# RP2040_Evaluation_Design.net
KiCad netlist of a schematic drawn in Altium Designer
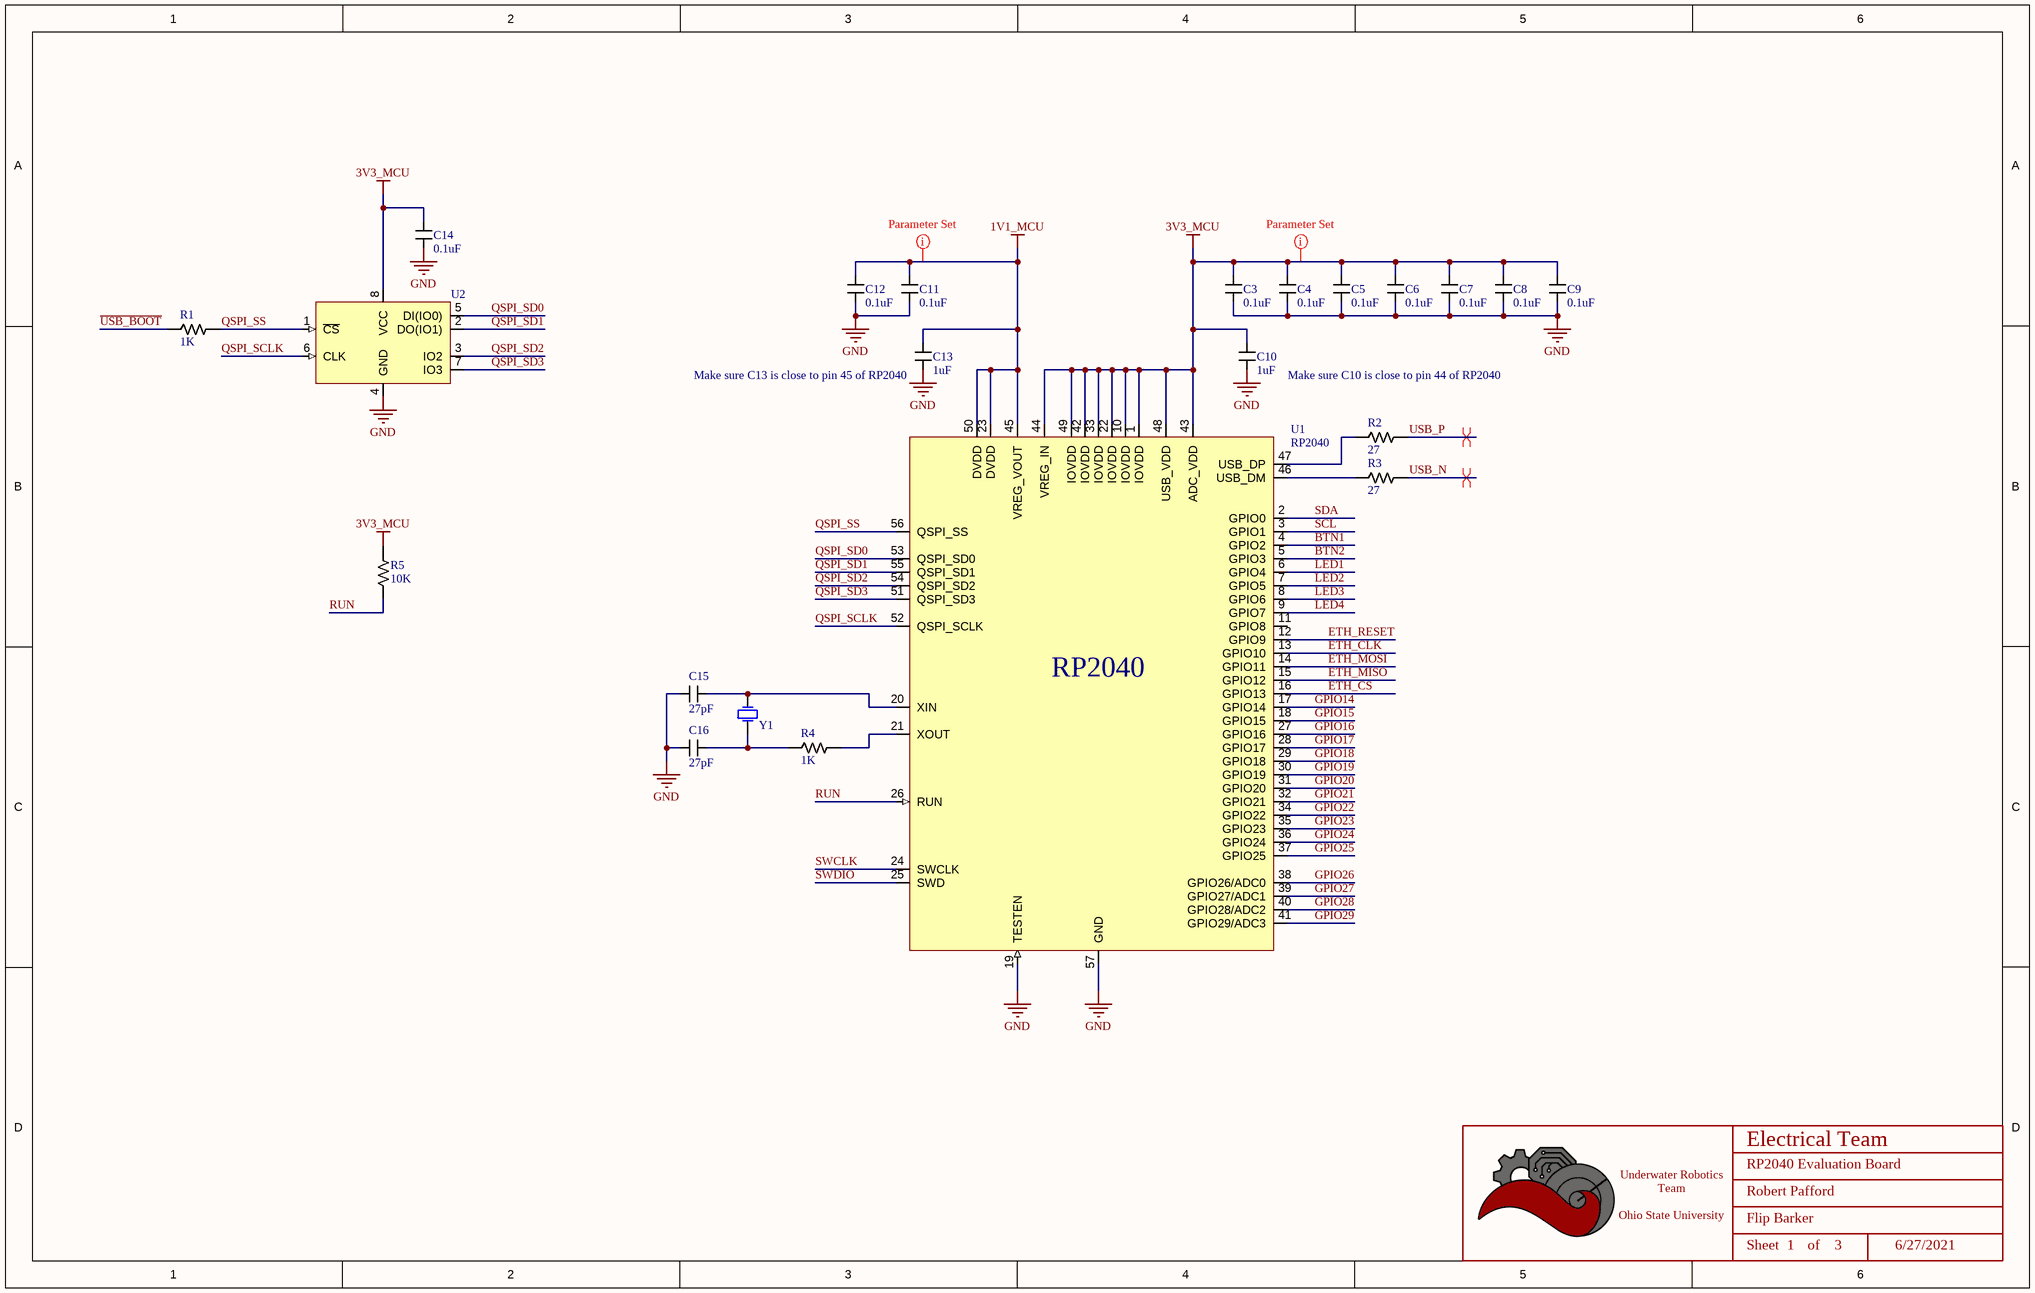
[diagram p0: RP2040_Evaluation_Design.SchDoc]

(export (version "E")
  (design (tool "Eeschema 10.0.6"))
  (components
    (comp (ref "C3")
      (value "0.1uF")
      (footprint "CAPACITOR_0603")
      (description "Cap 100nF 6.3V +/-10%\r\nCeramic 0603")
      (fields
        (field (name "TOLERANCE") "+/- 10%")
        (field (name "VOLTAGE") "6.3V")
        (field (name "MADE BY") "Flip B")
      )
      (libsource (lib "Capacitors") (part "CAPACITOR_0.1uF_0603"))
    )
    (comp (ref "C4")
      (value "0.1uF")
      (footprint "CAPACITOR_0603")
      (description "Cap 100nF 6.3V +/-10%\r\nCeramic 0603")
      (fields
        (field (name "TOLERANCE") "+/- 10%")
        (field (name "VOLTAGE") "6.3V")
        (field (name "MADE BY") "Flip B")
      )
      (libsource (lib "Capacitors") (part "CAPACITOR_0.1uF_0603"))
    )
    (comp (ref "C5")
      (value "0.1uF")
      (footprint "CAPACITOR_0603")
      (description "Cap 100nF 6.3V +/-10%\r\nCeramic 0603")
      (fields
        (field (name "TOLERANCE") "+/- 10%")
        (field (name "VOLTAGE") "6.3V")
        (field (name "MADE BY") "Flip B")
      )
      (libsource (lib "Capacitors") (part "CAPACITOR_0.1uF_0603"))
    )
    (comp (ref "C6")
      (value "0.1uF")
      (footprint "CAPACITOR_0603")
      (description "Cap 100nF 6.3V +/-10%\r\nCeramic 0603")
      (fields
        (field (name "TOLERANCE") "+/- 10%")
        (field (name "VOLTAGE") "6.3V")
        (field (name "MADE BY") "Flip B")
      )
      (libsource (lib "Capacitors") (part "CAPACITOR_0.1uF_0603"))
    )
    (comp (ref "C7")
      (value "0.1uF")
      (footprint "CAPACITOR_0603")
      (description "Cap 100nF 6.3V +/-10%\r\nCeramic 0603")
      (fields
        (field (name "TOLERANCE") "+/- 10%")
        (field (name "VOLTAGE") "6.3V")
        (field (name "MADE BY") "Flip B")
      )
      (libsource (lib "Capacitors") (part "CAPACITOR_0.1uF_0603"))
    )
    (comp (ref "C8")
      (value "0.1uF")
      (footprint "CAPACITOR_0603")
      (description "Cap 100nF 6.3V +/-10%\r\nCeramic 0603")
      (fields
        (field (name "TOLERANCE") "+/- 10%")
        (field (name "VOLTAGE") "6.3V")
        (field (name "MADE BY") "Flip B")
      )
      (libsource (lib "Capacitors") (part "CAPACITOR_0.1uF_0603"))
    )
    (comp (ref "C9")
      (value "0.1uF")
      (footprint "CAPACITOR_0603")
      (description "Cap 100nF 6.3V +/-10%\r\nCeramic 0603")
      (fields
        (field (name "TOLERANCE") "+/- 10%")
        (field (name "VOLTAGE") "6.3V")
        (field (name "MADE BY") "Flip B")
      )
      (libsource (lib "Capacitors") (part "CAPACITOR_0.1uF_0603"))
    )
    (comp (ref "C10")
      (value "1uF")
      (footprint "CAPACITOR_0603")
      (description "Cap 1uF 16V +/-10%\r\nCeramic 0603")
      (fields
        (field (name "TOLERANCE") "+/- 10%")
        (field (name "VOLTAGE") "16V")
        (field (name "MADE BY") "Flip B")
      )
      (libsource (lib "Capacitors") (part "CAPACITOR_1uF_0603"))
    )
    (comp (ref "C11")
      (value "0.1uF")
      (footprint "CAPACITOR_0603")
      (description "Cap 100nF 6.3V +/-10%\r\nCeramic 0603")
      (fields
        (field (name "TOLERANCE") "+/- 10%")
        (field (name "VOLTAGE") "6.3V")
        (field (name "MADE BY") "Flip B")
      )
      (libsource (lib "Capacitors") (part "CAPACITOR_0.1uF_0603"))
    )
    (comp (ref "C12")
      (value "0.1uF")
      (footprint "CAPACITOR_0603")
      (description "Cap 100nF 6.3V +/-10%\r\nCeramic 0603")
      (fields
        (field (name "TOLERANCE") "+/- 10%")
        (field (name "VOLTAGE") "6.3V")
        (field (name "MADE BY") "Flip B")
      )
      (libsource (lib "Capacitors") (part "CAPACITOR_0.1uF_0603"))
    )
    (comp (ref "C13")
      (value "1uF")
      (footprint "CAPACITOR_0603")
      (description "Cap 1uF 16V +/-10%\r\nCeramic 0603")
      (fields
        (field (name "TOLERANCE") "+/- 10%")
        (field (name "VOLTAGE") "16V")
        (field (name "MADE BY") "Flip B")
      )
      (libsource (lib "Capacitors") (part "CAPACITOR_1uF_0603"))
    )
    (comp (ref "C14")
      (value "0.1uF")
      (footprint "CAPACITOR_0603")
      (description "Cap 100nF 6.3V +/-10%\r\nCeramic 0603")
      (fields
        (field (name "TOLERANCE") "+/- 10%")
        (field (name "VOLTAGE") "6.3V")
        (field (name "MADE BY") "Flip B")
      )
      (libsource (lib "Capacitors") (part "CAPACITOR_0.1uF_0603"))
    )
    (comp (ref "C15")
      (value "27pF")
      (footprint "CAPACITOR_0603")
      (description "Cap 27pF 50V +/-5%\r\nCeramic 0603")
      (fields
        (field (name "TOLERANCE") "+/- 5%")
        (field (name "VOLTAGE") "50V")
        (field (name "MADE BY") "Flip B")
      )
      (libsource (lib "Capacitors") (part "CAPACITOR_0.000027uF_0603"))
    )
    (comp (ref "C16")
      (value "27pF")
      (footprint "CAPACITOR_0603")
      (description "Cap 27pF 50V +/-5%\r\nCeramic 0603")
      (fields
        (field (name "TOLERANCE") "+/- 5%")
        (field (name "VOLTAGE") "50V")
        (field (name "MADE BY") "Flip B")
      )
      (libsource (lib "Capacitors") (part "CAPACITOR_0.000027uF_0603"))
    )
    (comp (ref "R1")
      (value "1k Ohm 5% 1/8W")
      (footprint "RESISTOR_0603")
      (description "RES 1k OHM 5% 1/10W 0603")
      (fields
        (field (name "TOLERANCE") "+/- 5%")
        (field (name "VALUE  (OHMS)") "1K")
        (field (name "MADE BY") "Flip B")
      )
      (libsource (lib "Resistors") (part "RESISTOR_1K_0603"))
    )
    (comp (ref "R2")
      (value "27 Ohm 5% 1/8W")
      (footprint "RESISTOR_0603")
      (description "RES 27 OHM 5% 1/8W 0603")
      (fields
        (field (name "TOLERANCE") "+/- 5%")
        (field (name "VALUE  (OHMS)") "27")
        (field (name "MADE BY") "Flip B")
      )
      (libsource (lib "Resistors") (part "RESISTOR_27_0603"))
    )
    (comp (ref "R3")
      (value "27 Ohm 5% 1/8W")
      (footprint "RESISTOR_0603")
      (description "RES 27 OHM 5% 1/8W 0603")
      (fields
        (field (name "TOLERANCE") "+/- 5%")
        (field (name "VALUE  (OHMS)") "27")
        (field (name "MADE BY") "Flip B")
      )
      (libsource (lib "Resistors") (part "RESISTOR_27_0603"))
    )
    (comp (ref "R4")
      (value "1k Ohm 5% 1/8W")
      (footprint "RESISTOR_0603")
      (description "RES 1k OHM 5% 1/10W 0603")
      (fields
        (field (name "TOLERANCE") "+/- 5%")
        (field (name "VALUE  (OHMS)") "1K")
        (field (name "MADE BY") "Flip B")
      )
      (libsource (lib "Resistors") (part "RESISTOR_1K_0603"))
    )
    (comp (ref "R5")
      (value "10k Ohm 5% 1/10W")
      (footprint "RESISTOR_0603")
      (description "RES 10k OHM 5% 1/10W 0603")
      (fields
        (field (name "TOLERANCE") "+/- 5%")
        (field (name "VALUE  (OHMS)") "10K")
        (field (name "MADE BY") "Robert Pafford")
      )
      (libsource (lib "Resistors") (part "RESISTOR_10K_0603"))
    )
    (comp (ref "U1")
      (value "RP2040")
      (footprint "QFN-56 RP2040")
      (description "Raspberry Pi RP2040")
      (libsource (lib "UWRT") (part "RP2040"))
    )
    (comp (ref "U2")
      (value "W25Q128JVSIQ")
      (footprint "SOIC-8 W25QxJV")
      (description "IC FLASH 128MBIT SPI/QUAD 8SOIC")
      (libsource (lib "Integrated Circuits") (part "W25Q128JVSIQ"))
    )
    (comp (ref "Y1")
      (value "CRYSTAL_12MHZ")
      (footprint "CRYSTAL_THROUGH_HOLE")
      (description "CRYSTAL 12.0000MHZ 18PF TH")
      (libsource (lib "Crystals") (part "CRYSTAL_12MHZ"))
    )
  )
  (nets
    (net (code "1") (name "/BTN1") (class "Default")
      (node (ref "U1") (pin "4") (pinfunction "GPIO2_4") (pintype "bidirectional"))
    )
    (net (code "2") (name "/BTN2") (class "Default")
      (node (ref "U1") (pin "5") (pinfunction "GPIO3_5") (pintype "bidirectional"))
    )
    (net (code "3") (name "/ETH_CLK") (class "Default")
      (node (ref "U1") (pin "13") (pinfunction "GPIO10_13") (pintype "bidirectional"))
    )
    (net (code "4") (name "/ETH_CS") (class "Default")
      (node (ref "U1") (pin "16") (pinfunction "GPIO13_16") (pintype "bidirectional"))
    )
    (net (code "5") (name "/ETH_MISO") (class "Default")
      (node (ref "U1") (pin "15") (pinfunction "GPIO12_15") (pintype "bidirectional"))
    )
    (net (code "6") (name "/ETH_MOSI") (class "Default")
      (node (ref "U1") (pin "14") (pinfunction "GPIO11_14") (pintype "bidirectional"))
    )
    (net (code "7") (name "/ETH_RESET") (class "Default")
      (node (ref "U1") (pin "12") (pinfunction "GPIO9_12") (pintype "bidirectional"))
    )
    (net (code "8") (name "/GPIO14") (class "Default")
      (node (ref "U1") (pin "17") (pinfunction "GPIO14_17") (pintype "bidirectional"))
    )
    (net (code "9") (name "/GPIO15") (class "Default")
      (node (ref "U1") (pin "18") (pinfunction "GPIO15_18") (pintype "bidirectional"))
    )
    (net (code "10") (name "/GPIO16") (class "Default")
      (node (ref "U1") (pin "27") (pinfunction "GPIO16_27") (pintype "bidirectional"))
    )
    (net (code "11") (name "/GPIO17") (class "Default")
      (node (ref "U1") (pin "28") (pinfunction "GPIO17_28") (pintype "bidirectional"))
    )
    (net (code "12") (name "/GPIO18") (class "Default")
      (node (ref "U1") (pin "29") (pinfunction "GPIO18_29") (pintype "bidirectional"))
    )
    (net (code "13") (name "/GPIO19") (class "Default")
      (node (ref "U1") (pin "30") (pinfunction "GPIO19_30") (pintype "bidirectional"))
    )
    (net (code "14") (name "/GPIO20") (class "Default")
      (node (ref "U1") (pin "31") (pinfunction "GPIO20_31") (pintype "bidirectional"))
    )
    (net (code "15") (name "/GPIO21") (class "Default")
      (node (ref "U1") (pin "32") (pinfunction "GPIO21_32") (pintype "bidirectional"))
    )
    (net (code "16") (name "/GPIO22") (class "Default")
      (node (ref "U1") (pin "34") (pinfunction "GPIO22_34") (pintype "bidirectional"))
    )
    (net (code "17") (name "/GPIO23") (class "Default")
      (node (ref "U1") (pin "35") (pinfunction "GPIO23_35") (pintype "bidirectional"))
    )
    (net (code "18") (name "/GPIO24") (class "Default")
      (node (ref "U1") (pin "36") (pinfunction "GPIO24_36") (pintype "bidirectional"))
    )
    (net (code "19") (name "/GPIO25") (class "Default")
      (node (ref "U1") (pin "37") (pinfunction "GPIO25_37") (pintype "bidirectional"))
    )
    (net (code "20") (name "/GPIO26") (class "Default")
      (node (ref "U1") (pin "38") (pinfunction "GPIO26/ADC0_38") (pintype "bidirectional"))
    )
    (net (code "21") (name "/GPIO27") (class "Default")
      (node (ref "U1") (pin "39") (pinfunction "GPIO27/ADC1_39") (pintype "bidirectional"))
    )
    (net (code "22") (name "/GPIO28") (class "Default")
      (node (ref "U1") (pin "40") (pinfunction "GPIO28/ADC2_40") (pintype "bidirectional"))
    )
    (net (code "23") (name "/GPIO29") (class "Default")
      (node (ref "U1") (pin "41") (pinfunction "GPIO29/ADC3_41") (pintype "bidirectional"))
    )
    (net (code "24") (name "/LED1") (class "Default")
      (node (ref "U1") (pin "6") (pinfunction "GPIO4_6") (pintype "bidirectional"))
    )
    (net (code "25") (name "/LED2") (class "Default")
      (node (ref "U1") (pin "7") (pinfunction "GPIO5_7") (pintype "bidirectional"))
    )
    (net (code "26") (name "/LED3") (class "Default")
      (node (ref "U1") (pin "8") (pinfunction "GPIO6_8") (pintype "bidirectional"))
    )
    (net (code "27") (name "/LED4") (class "Default")
      (node (ref "U1") (pin "9") (pinfunction "GPIO7_9") (pintype "bidirectional"))
    )
    (net (code "28") (name "/QSPI_SCLK") (class "Default")
      (node (ref "U1") (pin "52") (pinfunction "QSPI_SCLK_52") (pintype "bidirectional"))
      (node (ref "U2") (pin "6") (pinfunction "CLK_6") (pintype "input"))
    )
    (net (code "29") (name "/QSPI_SD0") (class "Default")
      (node (ref "U1") (pin "53") (pinfunction "QSPI_SD0_53") (pintype "bidirectional"))
      (node (ref "U2") (pin "5") (pinfunction "DI(IO0)_5") (pintype "bidirectional"))
    )
    (net (code "30") (name "/QSPI_SD1") (class "Default")
      (node (ref "U1") (pin "55") (pinfunction "QSPI_SD1_55") (pintype "bidirectional"))
      (node (ref "U2") (pin "2") (pinfunction "DO(IO1)_2") (pintype "bidirectional"))
    )
    (net (code "31") (name "/QSPI_SD2") (class "Default")
      (node (ref "U1") (pin "54") (pinfunction "QSPI_SD2_54") (pintype "bidirectional"))
      (node (ref "U2") (pin "3") (pinfunction "IO2_3") (pintype "bidirectional"))
    )
    (net (code "32") (name "/QSPI_SD3") (class "Default")
      (node (ref "U1") (pin "51") (pinfunction "QSPI_SD3_51") (pintype "bidirectional"))
      (node (ref "U2") (pin "7") (pinfunction "IO3_7") (pintype "bidirectional"))
    )
    (net (code "33") (name "/QSPI_SS") (class "Default")
      (node (ref "R1") (pin "1") (pinfunction "1_1") (pintype "passive"))
      (node (ref "U1") (pin "56") (pinfunction "QSPI_SS_56") (pintype "bidirectional"))
      (node (ref "U2") (pin "1") (pinfunction "~{CS}_1") (pintype "input"))
    )
    (net (code "34") (name "/RUN") (class "Default")
      (node (ref "R5") (pin "2") (pinfunction "2_2") (pintype "passive"))
      (node (ref "U1") (pin "26") (pinfunction "RUN_26") (pintype "input"))
    )
    (net (code "35") (name "/SCL") (class "Default")
      (node (ref "U1") (pin "3") (pinfunction "GPIO1_3") (pintype "bidirectional"))
    )
    (net (code "36") (name "/SDA") (class "Default")
      (node (ref "U1") (pin "2") (pinfunction "GPIO0_2") (pintype "bidirectional"))
    )
    (net (code "37") (name "/SWCLK") (class "Default")
      (node (ref "U1") (pin "24") (pinfunction "SWCLK_24") (pintype "bidirectional"))
    )
    (net (code "38") (name "/SWDIO") (class "Default")
      (node (ref "U1") (pin "25") (pinfunction "SWD_25") (pintype "bidirectional"))
    )
    (net (code "39") (name "/USB_N") (class "Default")
      (node (ref "R3") (pin "1") (pinfunction "1_1") (pintype "passive"))
    )
    (net (code "40") (name "/USB_P") (class "Default")
      (node (ref "R2") (pin "1") (pinfunction "1_1") (pintype "passive"))
    )
    (net (code "41") (name "/~{USB_BOOT}") (class "Default")
      (node (ref "R1") (pin "2") (pinfunction "2_2") (pintype "passive"))
    )
    (net (code "42") (name "1V1_MCU") (class "Default")
      (node (ref "C11") (pin "1") (pinfunction "1_1") (pintype "passive"))
      (node (ref "C12") (pin "1") (pinfunction "1_1") (pintype "passive"))
      (node (ref "C13") (pin "1") (pinfunction "1_1") (pintype "passive"))
      (node (ref "U1") (pin "23") (pinfunction "DVDD_23") (pintype "power_in"))
      (node (ref "U1") (pin "45") (pinfunction "VREG_VOUT_45") (pintype "power_in"))
      (node (ref "U1") (pin "50") (pinfunction "DVDD_50") (pintype "power_in"))
    )
    (net (code "43") (name "3V3_MCU") (class "Default")
      (node (ref "C10") (pin "1") (pinfunction "1_1") (pintype "passive"))
      (node (ref "C14") (pin "1") (pinfunction "1_1") (pintype "passive"))
      (node (ref "C3") (pin "1") (pinfunction "1_1") (pintype "passive"))
      (node (ref "C4") (pin "1") (pinfunction "1_1") (pintype "passive"))
      (node (ref "C5") (pin "1") (pinfunction "1_1") (pintype "passive"))
      (node (ref "C6") (pin "1") (pinfunction "1_1") (pintype "passive"))
      (node (ref "C7") (pin "1") (pinfunction "1_1") (pintype "passive"))
      (node (ref "C8") (pin "1") (pinfunction "1_1") (pintype "passive"))
      (node (ref "C9") (pin "1") (pinfunction "1_1") (pintype "passive"))
      (node (ref "R5") (pin "1") (pinfunction "1_1") (pintype "passive"))
      (node (ref "U1") (pin "1") (pinfunction "IOVDD_1") (pintype "power_in"))
      (node (ref "U1") (pin "10") (pinfunction "IOVDD_10") (pintype "power_in"))
      (node (ref "U1") (pin "22") (pinfunction "IOVDD_22") (pintype "power_in"))
      (node (ref "U1") (pin "33") (pinfunction "IOVDD_33") (pintype "power_in"))
      (node (ref "U1") (pin "42") (pinfunction "IOVDD_42") (pintype "power_in"))
      (node (ref "U1") (pin "43") (pinfunction "ADC_VDD_43") (pintype "power_in"))
      (node (ref "U1") (pin "44") (pinfunction "VREG_IN_44") (pintype "power_in"))
      (node (ref "U1") (pin "48") (pinfunction "USB_VDD_48") (pintype "power_in"))
      (node (ref "U1") (pin "49") (pinfunction "IOVDD_49") (pintype "power_in"))
      (node (ref "U2") (pin "8") (pinfunction "VCC_8") (pintype "power_in"))
    )
    (net (code "44") (name "GND") (class "Default")
      (node (ref "C10") (pin "2") (pinfunction "2_2") (pintype "passive"))
      (node (ref "C11") (pin "2") (pinfunction "2_2") (pintype "passive"))
      (node (ref "C12") (pin "2") (pinfunction "2_2") (pintype "passive"))
      (node (ref "C13") (pin "2") (pinfunction "2_2") (pintype "passive"))
      (node (ref "C14") (pin "2") (pinfunction "2_2") (pintype "passive"))
      (node (ref "C15") (pin "2") (pinfunction "2_2") (pintype "passive"))
      (node (ref "C16") (pin "2") (pinfunction "2_2") (pintype "passive"))
      (node (ref "C3") (pin "2") (pinfunction "2_2") (pintype "passive"))
      (node (ref "C4") (pin "2") (pinfunction "2_2") (pintype "passive"))
      (node (ref "C5") (pin "2") (pinfunction "2_2") (pintype "passive"))
      (node (ref "C6") (pin "2") (pinfunction "2_2") (pintype "passive"))
      (node (ref "C7") (pin "2") (pinfunction "2_2") (pintype "passive"))
      (node (ref "C8") (pin "2") (pinfunction "2_2") (pintype "passive"))
      (node (ref "C9") (pin "2") (pinfunction "2_2") (pintype "passive"))
      (node (ref "U1") (pin "19") (pinfunction "TESTEN_19") (pintype "input"))
      (node (ref "U1") (pin "57") (pinfunction "GND_57") (pintype "power_in"))
      (node (ref "U2") (pin "4") (pinfunction "GND_4") (pintype "power_in"))
    )
    (net (code "45") (name "Net-(C16-Pad1)") (class "Default")
      (node (ref "C16") (pin "1") (pinfunction "1_1") (pintype "passive"))
      (node (ref "R4") (pin "2") (pinfunction "2_2") (pintype "passive"))
      (node (ref "Y1") (pin "1") (pinfunction "1_1") (pintype "passive"))
    )
    (net (code "46") (name "Net-(U1-USB_DM)") (class "Default")
      (node (ref "R3") (pin "2") (pinfunction "2_2") (pintype "passive"))
      (node (ref "U1") (pin "46") (pinfunction "USB_DM_46") (pintype "bidirectional"))
    )
    (net (code "47") (name "Net-(U1-USB_DP)") (class "Default")
      (node (ref "R2") (pin "2") (pinfunction "2_2") (pintype "passive"))
      (node (ref "U1") (pin "47") (pinfunction "USB_DP_47") (pintype "bidirectional"))
    )
    (net (code "48") (name "Net-(U1-XIN)") (class "Default")
      (node (ref "C15") (pin "1") (pinfunction "1_1") (pintype "passive"))
      (node (ref "U1") (pin "20") (pinfunction "XIN_20") (pintype "passive"))
      (node (ref "Y1") (pin "2") (pinfunction "2_2") (pintype "passive"))
    )
    (net (code "49") (name "Net-(U1-XOUT)") (class "Default")
      (node (ref "R4") (pin "1") (pinfunction "1_1") (pintype "passive"))
      (node (ref "U1") (pin "21") (pinfunction "XOUT_21") (pintype "passive"))
    )
    (net (code "50") (name "unconnected-(U1-GPIO8-Pad11)") (class "Default")
      (node (ref "U1") (pin "11") (pinfunction "GPIO8_11") (pintype "bidirectional"))
    )
  )
)
